# Hub_01.net
KiCad netlist of a schematic drawn in EAGLE
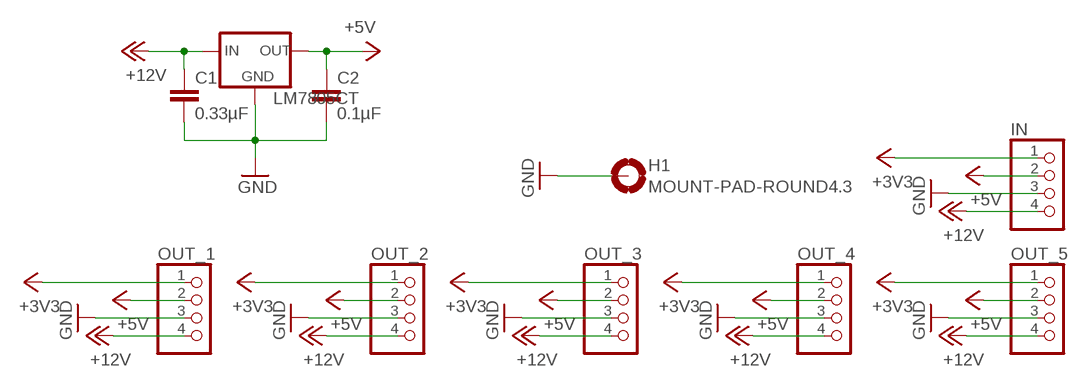
[diagram p0: schematic, sheet 1]

(export (version "E")
  (design (tool "Eeschema 10.0.6"))
  (components
    (comp (ref "C1")
      (value "0.33µF")
      (footprint "eagle-import:C025-024X044")
      (libsource (lib "eagle-import") (part "C-EU025-024X044"))
    )
    (comp (ref "C2")
      (value "0.1µF")
      (footprint "eagle-import:C025-024X044")
      (libsource (lib "eagle-import") (part "C-EU025-024X044"))
    )
    (comp (ref "H1")
      (value "MOUNT-PAD-ROUND4.3")
      (footprint "eagle-import:4,3-PAD")
      (libsource (lib "eagle-import") (part "MOUNT-PAD-ROUND4.3"))
    )
    (comp (ref "IN")
      (value "PINHD-1X4")
      (footprint "eagle-import:1X04")
      (libsource (lib "eagle-import") (part "PINHD-1X4"))
    )
    (comp (ref "LM7805CT")
      (value "78XXS")
      (footprint "eagle-import:78XXS")
      (libsource (lib "eagle-import") (part "78XXS"))
    )
    (comp (ref "OUT_1")
      (value "PINHD-1X4")
      (footprint "eagle-import:1X04")
      (libsource (lib "eagle-import") (part "PINHD-1X4"))
    )
    (comp (ref "OUT_2")
      (value "PINHD-1X4")
      (footprint "eagle-import:1X04")
      (libsource (lib "eagle-import") (part "PINHD-1X4"))
    )
    (comp (ref "OUT_3")
      (value "PINHD-1X4")
      (footprint "eagle-import:1X04")
      (libsource (lib "eagle-import") (part "PINHD-1X4"))
    )
    (comp (ref "OUT_4")
      (value "PINHD-1X4")
      (footprint "eagle-import:1X04")
      (libsource (lib "eagle-import") (part "PINHD-1X4"))
    )
    (comp (ref "OUT_5")
      (value "PINHD-1X4")
      (footprint "eagle-import:1X04")
      (libsource (lib "eagle-import") (part "PINHD-1X4"))
    )
  )
  (nets
    (net (code "1") (name "+3V3") (class "Default")
      (node (ref "IN") (pin "1") (pinfunction "1_1") (pintype "passive"))
      (node (ref "OUT_1") (pin "1") (pinfunction "1_1") (pintype "passive"))
      (node (ref "OUT_2") (pin "1") (pinfunction "1_1") (pintype "passive"))
      (node (ref "OUT_3") (pin "1") (pinfunction "1_1") (pintype "passive"))
      (node (ref "OUT_4") (pin "1") (pinfunction "1_1") (pintype "passive"))
      (node (ref "OUT_5") (pin "1") (pinfunction "1_1") (pintype "passive"))
    )
    (net (code "2") (name "+5V") (class "Default")
      (node (ref "C2") (pin "1") (pinfunction "1_1") (pintype "passive"))
      (node (ref "IN") (pin "2") (pinfunction "2_2") (pintype "passive"))
      (node (ref "LM7805CT") (pin "OUT") (pinfunction "OUT_OUT") (pintype "passive"))
      (node (ref "OUT_1") (pin "2") (pinfunction "2_2") (pintype "passive"))
      (node (ref "OUT_2") (pin "2") (pinfunction "2_2") (pintype "passive"))
      (node (ref "OUT_3") (pin "2") (pinfunction "2_2") (pintype "passive"))
      (node (ref "OUT_4") (pin "2") (pinfunction "2_2") (pintype "passive"))
      (node (ref "OUT_5") (pin "2") (pinfunction "2_2") (pintype "passive"))
    )
    (net (code "3") (name "+12V") (class "Default")
      (node (ref "C1") (pin "1") (pinfunction "1_1") (pintype "passive"))
      (node (ref "IN") (pin "4") (pinfunction "4_4") (pintype "passive"))
      (node (ref "LM7805CT") (pin "IN") (pinfunction "IN_IN") (pintype "input"))
      (node (ref "OUT_1") (pin "4") (pinfunction "4_4") (pintype "passive"))
      (node (ref "OUT_2") (pin "4") (pinfunction "4_4") (pintype "passive"))
      (node (ref "OUT_3") (pin "4") (pinfunction "4_4") (pintype "passive"))
      (node (ref "OUT_4") (pin "4") (pinfunction "4_4") (pintype "passive"))
      (node (ref "OUT_5") (pin "4") (pinfunction "4_4") (pintype "passive"))
    )
    (net (code "4") (name "GND") (class "Default")
      (node (ref "C1") (pin "2") (pinfunction "2_2") (pintype "passive"))
      (node (ref "C2") (pin "2") (pinfunction "2_2") (pintype "passive"))
      (node (ref "H1") (pin "B4,3") (pinfunction "MOUNT_B4,3") (pintype "passive"))
      (node (ref "IN") (pin "3") (pinfunction "3_3") (pintype "passive"))
      (node (ref "LM7805CT") (pin "GND") (pinfunction "GND_GND") (pintype "input"))
      (node (ref "OUT_1") (pin "3") (pinfunction "3_3") (pintype "passive"))
      (node (ref "OUT_2") (pin "3") (pinfunction "3_3") (pintype "passive"))
      (node (ref "OUT_3") (pin "3") (pinfunction "3_3") (pintype "passive"))
      (node (ref "OUT_4") (pin "3") (pinfunction "3_3") (pintype "passive"))
      (node (ref "OUT_5") (pin "3") (pinfunction "3_3") (pintype "passive"))
    )
  )
)
